# attiny45-microcontrol.net
KiCad netlist of a schematic drawn in EAGLE
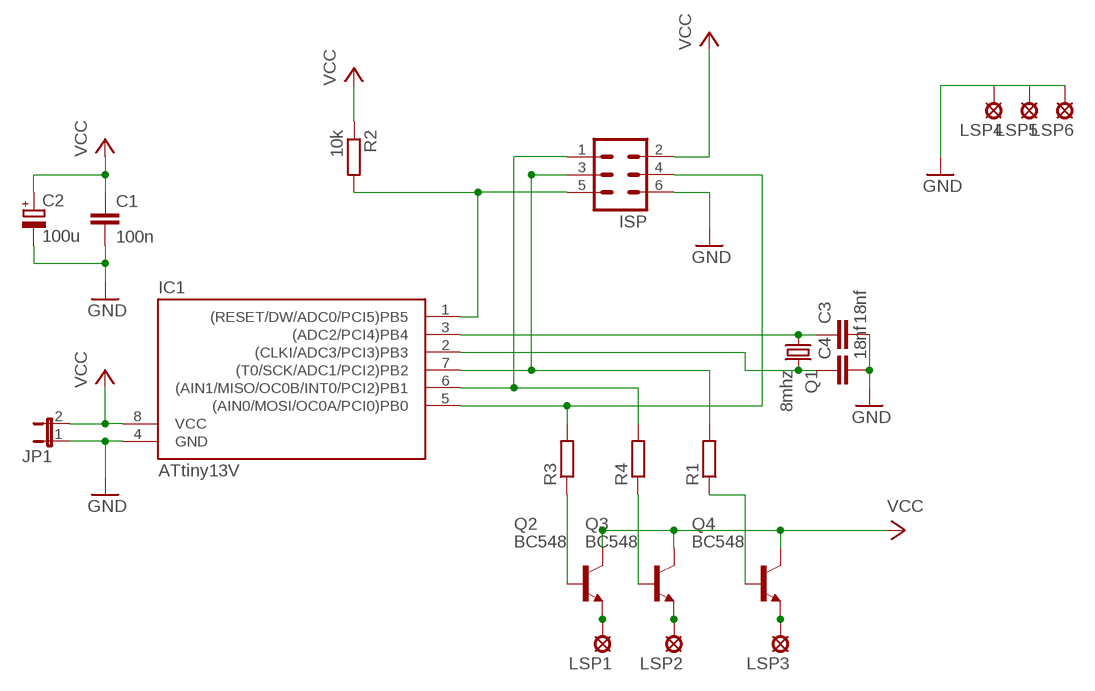
[diagram p0: schematic, sheet 1]

(export (version "E")
  (design (tool "Eeschema 10.0.6"))
  (components
    (comp (ref "C1")
      (value "100n")
      (footprint "eagle-import:C025-025X050")
      (libsource (lib "eagle-import") (part "C-EU025-025X050"))
    )
    (comp (ref "C2")
      (value "100u")
      (footprint "eagle-import:E2,5-6E")
      (libsource (lib "eagle-import") (part "CPOL-EUE2,5-6E"))
    )
    (comp (ref "C3")
      (value "18nf")
      (footprint "eagle-import:C5B2.5")
      (libsource (lib "eagle-import") (part "C5/2.5"))
    )
    (comp (ref "C4")
      (value "18nf")
      (footprint "eagle-import:C5B2.5")
      (libsource (lib "eagle-import") (part "C5/2.5"))
    )
    (comp (ref "IC1")
      (value "ATtiny13V")
      (footprint "eagle-import:DIL08")
      (libsource (lib "eagle-import") (part "ATTINY13P-20"))
    )
    (comp (ref "ISP")
      (value "MA03-2")
      (footprint "eagle-import:MA03-2")
      (libsource (lib "eagle-import") (part "MA03-2"))
    )
    (comp (ref "JP1")
      (value "JP1E")
      (footprint "eagle-import:JP1")
      (libsource (lib "eagle-import") (part "JP1E"))
    )
    (comp (ref "LSP1")
      (value "LSP10")
      (footprint "eagle-import:LSP10")
      (libsource (lib "eagle-import") (part "LSP10"))
    )
    (comp (ref "LSP2")
      (value "LSP10")
      (footprint "eagle-import:LSP10")
      (libsource (lib "eagle-import") (part "LSP10"))
    )
    (comp (ref "LSP3")
      (value "LSP10")
      (footprint "eagle-import:LSP10")
      (libsource (lib "eagle-import") (part "LSP10"))
    )
    (comp (ref "LSP4")
      (value "LSP10")
      (footprint "eagle-import:LSP10")
      (libsource (lib "eagle-import") (part "LSP10"))
    )
    (comp (ref "LSP5")
      (value "LSP10")
      (footprint "eagle-import:LSP10")
      (libsource (lib "eagle-import") (part "LSP10"))
    )
    (comp (ref "LSP6")
      (value "LSP10")
      (footprint "eagle-import:LSP10")
      (libsource (lib "eagle-import") (part "LSP10"))
    )
    (comp (ref "Q1")
      (value "8mhz")
      (footprint "eagle-import:HC18U-V")
      (libsource (lib "eagle-import") (part "CRYSTALHC18U-V"))
    )
    (comp (ref "Q2")
      (value "BC548")
      (footprint "eagle-import:TO92-EBC")
      (libsource (lib "eagle-import") (part "BC548"))
    )
    (comp (ref "Q3")
      (value "BC548")
      (footprint "eagle-import:TO92-EBC")
      (libsource (lib "eagle-import") (part "BC548"))
    )
    (comp (ref "Q4")
      (value "BC548")
      (footprint "eagle-import:TO92-EBC")
      (libsource (lib "eagle-import") (part "BC548"))
    )
    (comp (ref "R1")
      (value "R-EU_0204/5")
      (footprint "eagle-import:0204_5")
      (libsource (lib "eagle-import") (part "R-EU_0204/5"))
    )
    (comp (ref "R2")
      (value "10k")
      (footprint "eagle-import:0204_7")
      (libsource (lib "eagle-import") (part "R-EU_0204/7"))
    )
    (comp (ref "R3")
      (value "R-EU_0204/5")
      (footprint "eagle-import:0204_5")
      (libsource (lib "eagle-import") (part "R-EU_0204/5"))
    )
    (comp (ref "R4")
      (value "R-EU_0204/5")
      (footprint "eagle-import:0204_5")
      (libsource (lib "eagle-import") (part "R-EU_0204/5"))
    )
  )
  (nets
    (net (code "1") (name "GND") (class "Default")
      (node (ref "C1") (pin "2") (pinfunction "2_2") (pintype "passive"))
      (node (ref "C2") (pin "-") (pinfunction "-_-") (pintype "passive"))
      (node (ref "C3") (pin "2") (pinfunction "2_2") (pintype "passive"))
      (node (ref "C4") (pin "2") (pinfunction "2_2") (pintype "passive"))
      (node (ref "IC1") (pin "4") (pinfunction "GND_4") (pintype "power_in"))
      (node (ref "ISP") (pin "6") (pinfunction "6_6") (pintype "passive"))
      (node (ref "JP1") (pin "1") (pinfunction "1_1") (pintype "passive"))
      (node (ref "LSP4") (pin "MP") (pinfunction "MP_MP") (pintype "passive"))
      (node (ref "LSP5") (pin "MP") (pinfunction "MP_MP") (pintype "passive"))
      (node (ref "LSP6") (pin "MP") (pinfunction "MP_MP") (pintype "passive"))
    )
    (net (code "2") (name "Net-(IC1-(ADC2{slash}PCI4)PB4)") (class "Default")
      (node (ref "C3") (pin "1") (pinfunction "1_1") (pintype "passive"))
      (node (ref "IC1") (pin "3") (pinfunction "(ADC2/PCI4)PB4_3") (pintype "bidirectional"))
      (node (ref "Q1") (pin "1") (pinfunction "1_1") (pintype "passive"))
    )
    (net (code "3") (name "Net-(IC1-(AIN0{slash}MOSI{slash}OC0A{slash}PCI0)PB0)") (class "Default")
      (node (ref "IC1") (pin "5") (pinfunction "(AIN0/MOSI/OC0A/PCI0)PB0_5") (pintype "bidirectional"))
      (node (ref "ISP") (pin "4") (pinfunction "4_4") (pintype "passive"))
      (node (ref "R3") (pin "2") (pinfunction "2_2") (pintype "passive"))
    )
    (net (code "4") (name "Net-(IC1-(AIN1{slash}MISO{slash}OC0B{slash}INT0{slash}PCI2)PB1)") (class "Default")
      (node (ref "IC1") (pin "6") (pinfunction "(AIN1/MISO/OC0B/INT0/PCI2)PB1_6") (pintype "bidirectional"))
      (node (ref "ISP") (pin "1") (pinfunction "1_1") (pintype "passive"))
      (node (ref "R4") (pin "2") (pinfunction "2_2") (pintype "passive"))
    )
    (net (code "5") (name "Net-(IC1-(CLKI{slash}ADC3{slash}PCI3)PB3)") (class "Default")
      (node (ref "C4") (pin "1") (pinfunction "1_1") (pintype "passive"))
      (node (ref "IC1") (pin "2") (pinfunction "(CLKI/ADC3/PCI3)PB3_2") (pintype "bidirectional"))
      (node (ref "Q1") (pin "2") (pinfunction "2_2") (pintype "passive"))
    )
    (net (code "6") (name "Net-(IC1-(RESET{slash}DW{slash}ADC0{slash}PCI5)PB5)") (class "Default")
      (node (ref "IC1") (pin "1") (pinfunction "(RESET/DW/ADC0/PCI5)PB5_1") (pintype "bidirectional"))
      (node (ref "ISP") (pin "5") (pinfunction "5_5") (pintype "passive"))
      (node (ref "R2") (pin "2") (pinfunction "2_2") (pintype "passive"))
    )
    (net (code "7") (name "Net-(IC1-(T0{slash}SCK{slash}ADC1{slash}PCI2)PB2)") (class "Default")
      (node (ref "IC1") (pin "7") (pinfunction "(T0/SCK/ADC1/PCI2)PB2_7") (pintype "bidirectional"))
      (node (ref "ISP") (pin "3") (pinfunction "3_3") (pintype "passive"))
      (node (ref "R1") (pin "2") (pinfunction "2_2") (pintype "passive"))
    )
    (net (code "8") (name "Net-(LSP1-PadMP)") (class "Default")
      (node (ref "LSP1") (pin "MP") (pinfunction "MP_MP") (pintype "passive"))
      (node (ref "Q2") (pin "E") (pinfunction "E_E") (pintype "passive"))
    )
    (net (code "9") (name "Net-(LSP2-PadMP)") (class "Default")
      (node (ref "LSP2") (pin "MP") (pinfunction "MP_MP") (pintype "passive"))
      (node (ref "Q3") (pin "E") (pinfunction "E_E") (pintype "passive"))
    )
    (net (code "10") (name "Net-(LSP3-PadMP)") (class "Default")
      (node (ref "LSP3") (pin "MP") (pinfunction "MP_MP") (pintype "passive"))
      (node (ref "Q4") (pin "E") (pinfunction "E_E") (pintype "passive"))
    )
    (net (code "11") (name "Net-(Q2-PadB)") (class "Default")
      (node (ref "Q2") (pin "B") (pinfunction "B_B") (pintype "passive"))
      (node (ref "R3") (pin "1") (pinfunction "1_1") (pintype "passive"))
    )
    (net (code "12") (name "Net-(Q3-PadB)") (class "Default")
      (node (ref "Q3") (pin "B") (pinfunction "B_B") (pintype "passive"))
      (node (ref "R4") (pin "1") (pinfunction "1_1") (pintype "passive"))
    )
    (net (code "13") (name "Net-(Q4-PadB)") (class "Default")
      (node (ref "Q4") (pin "B") (pinfunction "B_B") (pintype "passive"))
      (node (ref "R1") (pin "1") (pinfunction "1_1") (pintype "passive"))
    )
    (net (code "14") (name "VCC") (class "Default")
      (node (ref "C1") (pin "1") (pinfunction "1_1") (pintype "passive"))
      (node (ref "C2") (pin "+") (pinfunction "+_+") (pintype "passive"))
      (node (ref "IC1") (pin "8") (pinfunction "VCC_8") (pintype "power_in"))
      (node (ref "ISP") (pin "2") (pinfunction "2_2") (pintype "passive"))
      (node (ref "JP1") (pin "2") (pinfunction "2_2") (pintype "passive"))
      (node (ref "Q2") (pin "C") (pinfunction "C_C") (pintype "passive"))
      (node (ref "Q3") (pin "C") (pinfunction "C_C") (pintype "passive"))
      (node (ref "Q4") (pin "C") (pinfunction "C_C") (pintype "passive"))
      (node (ref "R2") (pin "1") (pinfunction "1_1") (pintype "passive"))
    )
  )
)
